# design1.net
KiCad netlist of a schematic drawn in EAGLE
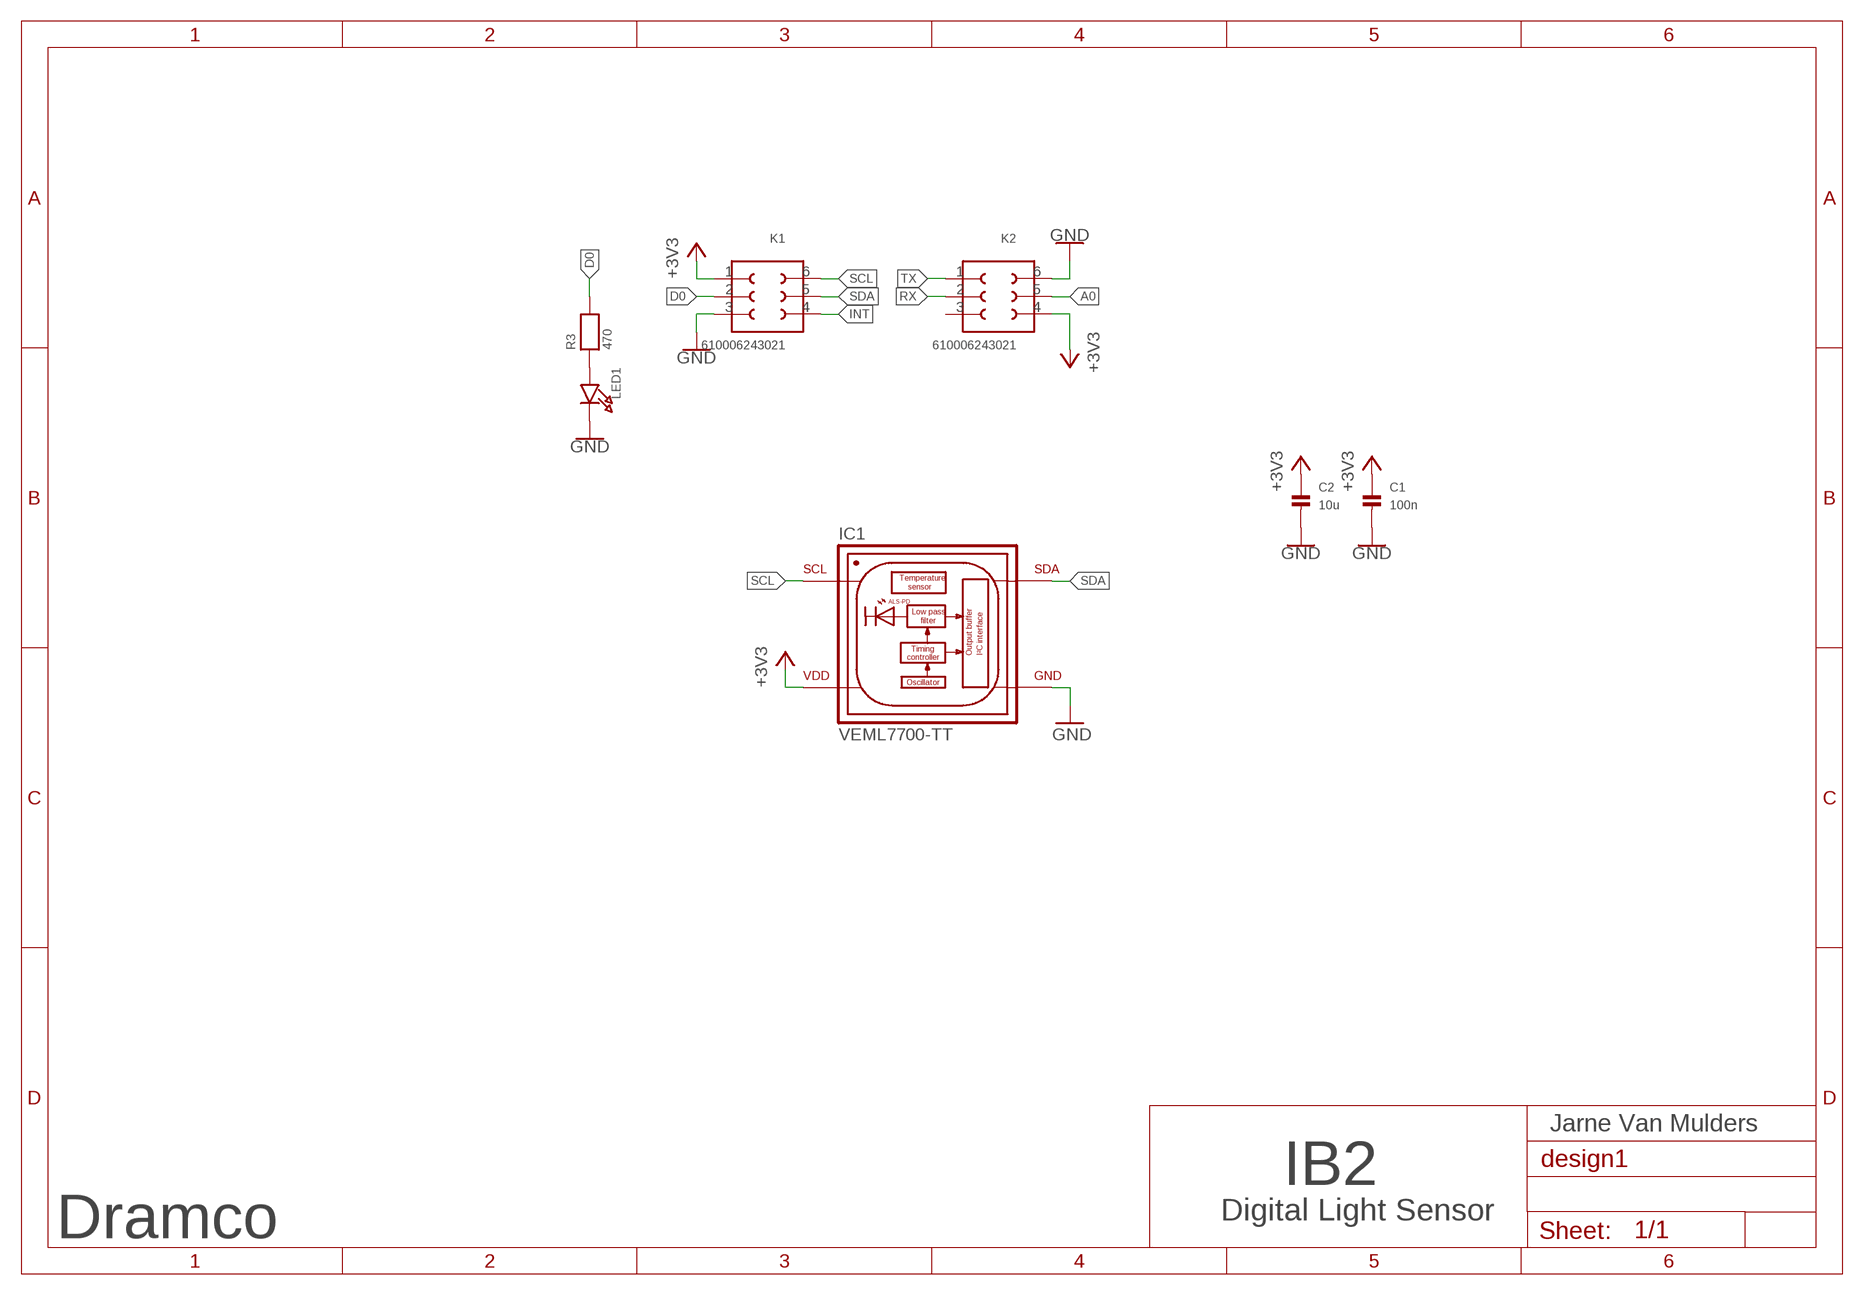
[diagram p0: schematic, sheet 1]

(export (version "E")
  (design (tool "Eeschema 10.0.6"))
  (components
    (comp (ref "C1")
      (value "100n")
      (footprint "eagle-import:0603")
      (libsource (lib "eagle-import") (part "CAP_CERAMIC0603"))
    )
    (comp (ref "C2")
      (value "10u")
      (footprint "eagle-import:0805")
      (libsource (lib "eagle-import") (part "CAP_CERAMIC0805"))
    )
    (comp (ref "IC1")
      (value "VEML7700-TT")
      (footprint "eagle-import:XDCR_VEML7700-TT")
      (fields (field (name "MF") "Vishay Semiconductor"))
      (libsource (lib "eagle-import") (part "VEML7700-TT"))
    )
    (comp (ref "K1")
      (value "610006243021")
      (footprint "eagle-import:610006243021")
      (libsource (lib "eagle-import") (part "610006243021"))
    )
    (comp (ref "K2")
      (value "610006243021")
      (footprint "eagle-import:610006243021")
      (libsource (lib "eagle-import") (part "610006243021"))
    )
    (comp (ref "LED1")
      (value "LED0805")
      (footprint "eagle-import:CHIPLED_0805")
      (libsource (lib "eagle-import") (part "LED0805"))
    )
    (comp (ref "R3")
      (value "470")
      (footprint "eagle-import:0603")
      (libsource (lib "eagle-import") (part "RESISTOR0603"))
    )
  )
  (nets
    (net (code "1") (name "+3V3") (class "Default")
      (node (ref "C1") (pin "1") (pinfunction "P$1_1") (pintype "passive"))
      (node (ref "C2") (pin "1") (pinfunction "P$1_1") (pintype "passive"))
      (node (ref "IC1") (pin "2") (pinfunction "VDD_2") (pintype "power_in"))
      (node (ref "K1") (pin "1") (pinfunction "1_1") (pintype "passive"))
      (node (ref "K2") (pin "4") (pinfunction "4_4") (pintype "passive"))
    )
    (net (code "2") (name "A0") (class "Default")
      (node (ref "K2") (pin "5") (pinfunction "5_5") (pintype "passive"))
    )
    (net (code "3") (name "D0") (class "Default")
      (node (ref "K1") (pin "2") (pinfunction "2_2") (pintype "passive"))
      (node (ref "R3") (pin "2") (pinfunction "2_2") (pintype "passive"))
    )
    (net (code "4") (name "GND") (class "Default")
      (node (ref "C1") (pin "2") (pinfunction "P$2_2") (pintype "passive"))
      (node (ref "C2") (pin "2") (pinfunction "P$2_2") (pintype "passive"))
      (node (ref "IC1") (pin "3") (pinfunction "GND_3") (pintype "power_in"))
      (node (ref "K1") (pin "3") (pinfunction "3_3") (pintype "passive"))
      (node (ref "K2") (pin "6") (pinfunction "6_6") (pintype "passive"))
      (node (ref "LED1") (pin "C") (pinfunction "C_C") (pintype "passive"))
    )
    (net (code "5") (name "INT") (class "Default")
      (node (ref "K1") (pin "4") (pinfunction "4_4") (pintype "passive"))
    )
    (net (code "6") (name "Net-(LED1-PadA)") (class "Default")
      (node (ref "LED1") (pin "A") (pinfunction "A_A") (pintype "passive"))
      (node (ref "R3") (pin "1") (pinfunction "1_1") (pintype "passive"))
    )
    (net (code "7") (name "RX") (class "Default")
      (node (ref "K2") (pin "2") (pinfunction "2_2") (pintype "passive"))
    )
    (net (code "8") (name "SCL") (class "Default")
      (node (ref "IC1") (pin "1") (pinfunction "SCL_1") (pintype "input"))
      (node (ref "K1") (pin "6") (pinfunction "6_6") (pintype "passive"))
    )
    (net (code "9") (name "SDA") (class "Default")
      (node (ref "IC1") (pin "4") (pinfunction "SDA_4") (pintype "bidirectional"))
      (node (ref "K1") (pin "5") (pinfunction "5_5") (pintype "passive"))
    )
    (net (code "10") (name "TX") (class "Default")
      (node (ref "K2") (pin "1") (pinfunction "1_1") (pintype "passive"))
    )
    (net (code "11") (name "unconnected-(K2-Pad3)") (class "Default")
      (node (ref "K2") (pin "3") (pinfunction "3_3") (pintype "passive"))
    )
  )
)
